# Sheet1.net
KiCad netlist of a schematic drawn in Altium Designer
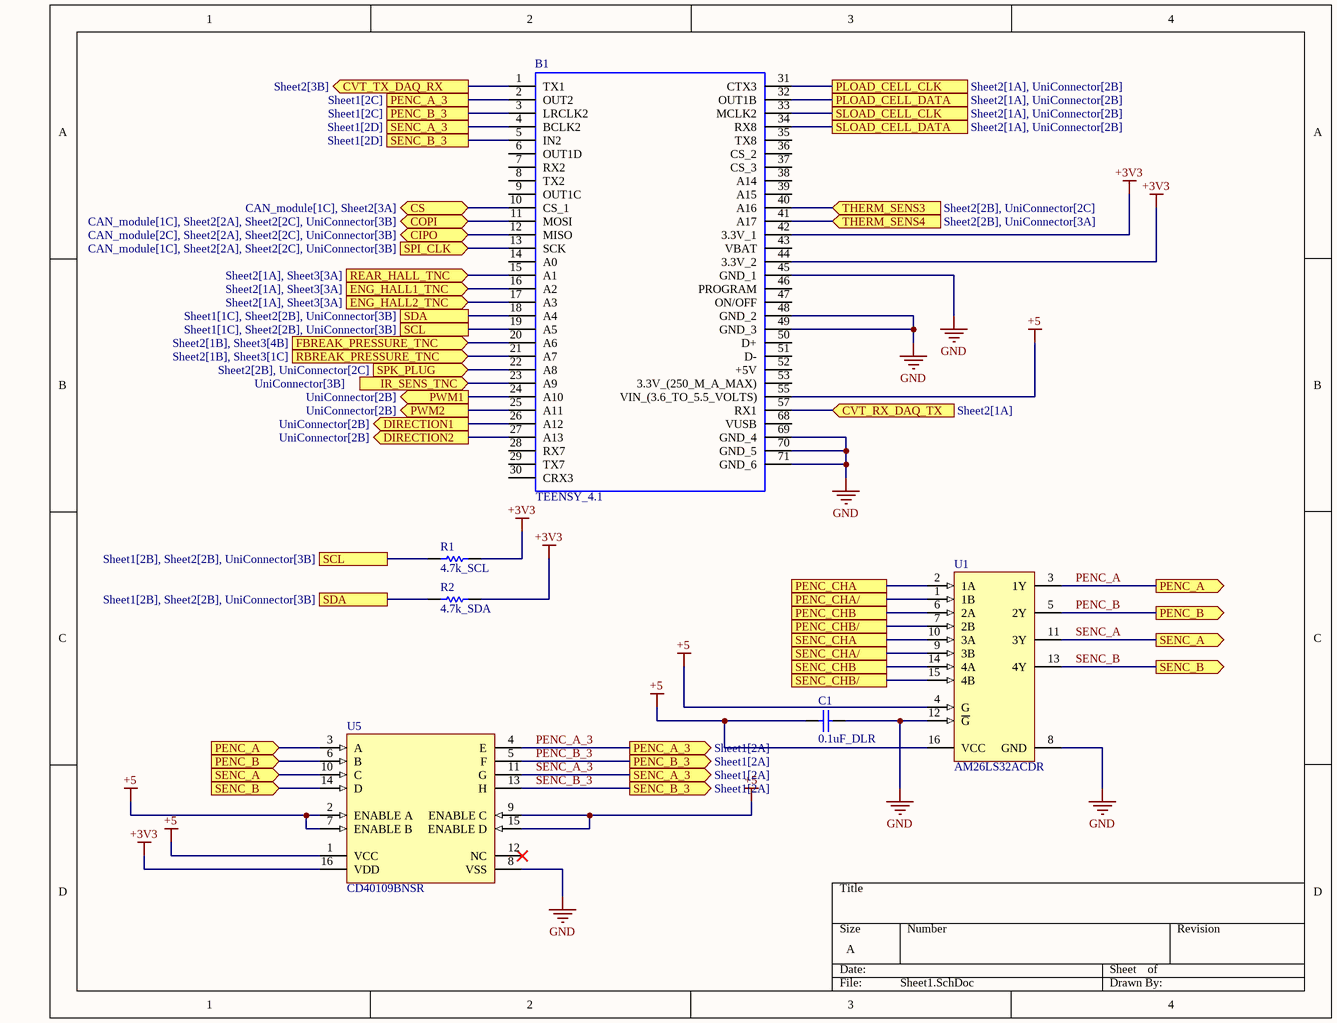
[diagram p0: Sheet1.SchDoc]

(export (version "E")
  (design (tool "Eeschema 10.0.6"))
  (components
    (comp (ref "B1")
      (value "TEENSY_4.1")
      (footprint "TEENSY41")
      (description "Teensy 4.1 Development Board")
      (fields (field (name "MANUFACTURER_PART_NUMBER") "TEENSY 4.1"))
      (libsource (lib "TEENSY_4.1") (part "TEENSY_4.1"))
    )
    (comp (ref "C1")
      (value "0.1uF_DLR")
      (footprint "CAPC2013X94X50LL20T25")
      (fields
        (field (name "MANUFACTURER") "AVX Interconnect / Elco")
        (field (name "PART NUMBER") "08055A6R2CAT2A")
      )
      (libsource (lib "Altium Content Vault") (part "CAP"))
    )
    (comp (ref "R1")
      (value "4.7k_SCL")
      (footprint "RESC2013X60X40LL20T25")
      (fields (field (name "MANUFACTURER") "Panasonic") (field (name "PART NUMBER") "ERA6AEB7870V"))
      (libsource (lib "Altium Content Vault") (part "RES"))
    )
    (comp (ref "R2")
      (value "4.7k_SDA")
      (footprint "RESC2013X60X40LL20T25")
      (fields (field (name "MANUFACTURER") "Panasonic") (field (name "PART NUMBER") "ERA6AEB7870V"))
      (libsource (lib "Altium Content Vault") (part "RES"))
    )
    (comp (ref "U1")
      (value "AM26LS32ACDR")
      (footprint "D0016A_M")
      (fields (field (name "MANUFACTURER") "Texas Instruments"))
      (libsource (lib "Altium Content Vault") (part "TI-AM26LS32AC-SOIC_D-16"))
    )
    (comp (ref "U5")
      (value "CD40109BNSR")
      (footprint "NS0016A_N")
      (fields (field (name "MANUFACTURER") "Texas Instruments"))
      (libsource (lib "Altium Content Vault") (part "TI-CD40109B-16"))
    )
  )
  (nets
    (net (code "1") (name "+3V3") (class "Default")
      (node (ref "B1") (pin "42") (pinfunction "3.3V_1_42") (pintype "passive"))
      (node (ref "B1") (pin "44") (pinfunction "3.3V_2_44") (pintype "passive"))
      (node (ref "R1") (pin "2") (pinfunction "2_2") (pintype "passive"))
      (node (ref "R2") (pin "2") (pinfunction "2_2") (pintype "passive"))
      (node (ref "U5") (pin "16") (pinfunction "VDD_16") (pintype "power_in"))
    )
    (net (code "2") (name "+5") (class "Default")
      (node (ref "B1") (pin "55") (pinfunction "VIN_(3.6_TO_5.5_VOLTS)_55") (pintype "passive"))
      (node (ref "C1") (pin "1") (pinfunction "1_1") (pintype "passive"))
      (node (ref "U1") (pin "16") (pinfunction "VCC_16") (pintype "power_in"))
      (node (ref "U1") (pin "4") (pinfunction "G_4") (pintype "input"))
      (node (ref "U5") (pin "1") (pinfunction "VCC_1") (pintype "power_in"))
      (node (ref "U5") (pin "15") (pinfunction "ENABLE_D_15") (pintype "input"))
      (node (ref "U5") (pin "2") (pinfunction "ENABLE_A_2") (pintype "input"))
      (node (ref "U5") (pin "7") (pinfunction "ENABLE_B_7") (pintype "input"))
      (node (ref "U5") (pin "9") (pinfunction "ENABLE_C_9") (pintype "input"))
    )
    (net (code "3") (name "/CIPO") (class "Default")
      (node (ref "B1") (pin "12") (pinfunction "MISO_12") (pintype "passive"))
    )
    (net (code "4") (name "/COPI") (class "Default")
      (node (ref "B1") (pin "11") (pinfunction "MOSI_11") (pintype "passive"))
    )
    (net (code "5") (name "/CS") (class "Default")
      (node (ref "B1") (pin "10") (pinfunction "CS_1_10") (pintype "passive"))
    )
    (net (code "6") (name "/CVT_RX_DAQ_TX") (class "Default")
      (node (ref "B1") (pin "57") (pinfunction "RX1_57") (pintype "passive"))
    )
    (net (code "7") (name "/CVT_TX_DAQ_RX") (class "Default")
      (node (ref "B1") (pin "1") (pinfunction "TX1_1") (pintype "passive"))
    )
    (net (code "8") (name "/DIRECTION1") (class "Default")
      (node (ref "B1") (pin "26") (pinfunction "A12_26") (pintype "passive"))
    )
    (net (code "9") (name "/DIRECTION2") (class "Default")
      (node (ref "B1") (pin "27") (pinfunction "A13_27") (pintype "passive"))
    )
    (net (code "10") (name "/ENG_HALL1_TNC") (class "Default")
      (node (ref "B1") (pin "16") (pinfunction "A2_16") (pintype "passive"))
    )
    (net (code "11") (name "/ENG_HALL2_TNC") (class "Default")
      (node (ref "B1") (pin "17") (pinfunction "A3_17") (pintype "passive"))
    )
    (net (code "12") (name "/FBREAK_PRESSURE_TNC") (class "Default")
      (node (ref "B1") (pin "20") (pinfunction "A6_20") (pintype "passive"))
    )
    (net (code "13") (name "/IR_SENS_TNC") (class "Default")
      (node (ref "B1") (pin "23") (pinfunction "A9_23") (pintype "passive"))
    )
    (net (code "14") (name "/PENC_A") (class "Default")
      (node (ref "U1") (pin "3") (pinfunction "1Y_3") (pintype "tri_state"))
      (node (ref "U5") (pin "3") (pinfunction "A_3") (pintype "input"))
    )
    (net (code "15") (name "/PENC_A_3") (class "Default")
      (node (ref "B1") (pin "2") (pinfunction "OUT2_2") (pintype "passive"))
      (node (ref "U5") (pin "4") (pinfunction "E_4") (pintype "tri_state"))
    )
    (net (code "16") (name "/PENC_B") (class "Default")
      (node (ref "U1") (pin "5") (pinfunction "2Y_5") (pintype "tri_state"))
      (node (ref "U5") (pin "6") (pinfunction "B_6") (pintype "input"))
    )
    (net (code "17") (name "/PENC_B_3") (class "Default")
      (node (ref "B1") (pin "3") (pinfunction "LRCLK2_3") (pintype "passive"))
      (node (ref "U5") (pin "5") (pinfunction "F_5") (pintype "tri_state"))
    )
    (net (code "18") (name "/PENC_CHA") (class "Default")
      (node (ref "U1") (pin "2") (pinfunction "1A_2") (pintype "input"))
    )
    (net (code "19") (name "/PENC_CHA{slash}") (class "Default")
      (node (ref "U1") (pin "1") (pinfunction "1B_1") (pintype "input"))
    )
    (net (code "20") (name "/PENC_CHB") (class "Default")
      (node (ref "U1") (pin "6") (pinfunction "2A_6") (pintype "input"))
    )
    (net (code "21") (name "/PENC_CHB{slash}") (class "Default")
      (node (ref "U1") (pin "7") (pinfunction "2B_7") (pintype "input"))
    )
    (net (code "22") (name "/PLOAD_CELL_CLK") (class "Default")
      (node (ref "B1") (pin "31") (pinfunction "CTX3_31") (pintype "passive"))
    )
    (net (code "23") (name "/PLOAD_CELL_DATA") (class "Default")
      (node (ref "B1") (pin "32") (pinfunction "OUT1B_32") (pintype "passive"))
    )
    (net (code "24") (name "/PWM1") (class "Default")
      (node (ref "B1") (pin "24") (pinfunction "A10_24") (pintype "passive"))
    )
    (net (code "25") (name "/PWM2") (class "Default")
      (node (ref "B1") (pin "25") (pinfunction "A11_25") (pintype "passive"))
    )
    (net (code "26") (name "/RBREAK_PRESSURE_TNC") (class "Default")
      (node (ref "B1") (pin "21") (pinfunction "A7_21") (pintype "passive"))
    )
    (net (code "27") (name "/REAR_HALL_TNC") (class "Default")
      (node (ref "B1") (pin "15") (pinfunction "A1_15") (pintype "passive"))
    )
    (net (code "28") (name "/SCL") (class "Default")
      (node (ref "B1") (pin "19") (pinfunction "A5_19") (pintype "passive"))
      (node (ref "R1") (pin "1") (pinfunction "1_1") (pintype "passive"))
    )
    (net (code "29") (name "/SDA") (class "Default")
      (node (ref "B1") (pin "18") (pinfunction "A4_18") (pintype "passive"))
      (node (ref "R2") (pin "1") (pinfunction "1_1") (pintype "passive"))
    )
    (net (code "30") (name "/SENC_A") (class "Default")
      (node (ref "U1") (pin "11") (pinfunction "3Y_11") (pintype "tri_state"))
      (node (ref "U5") (pin "10") (pinfunction "C_10") (pintype "input"))
    )
    (net (code "31") (name "/SENC_A_3") (class "Default")
      (node (ref "B1") (pin "4") (pinfunction "BCLK2_4") (pintype "passive"))
      (node (ref "U5") (pin "11") (pinfunction "G_11") (pintype "tri_state"))
    )
    (net (code "32") (name "/SENC_B") (class "Default")
      (node (ref "U1") (pin "13") (pinfunction "4Y_13") (pintype "tri_state"))
      (node (ref "U5") (pin "14") (pinfunction "D_14") (pintype "input"))
    )
    (net (code "33") (name "/SENC_B_3") (class "Default")
      (node (ref "B1") (pin "5") (pinfunction "IN2_5") (pintype "passive"))
      (node (ref "U5") (pin "13") (pinfunction "H_13") (pintype "tri_state"))
    )
    (net (code "34") (name "/SENC_CHA") (class "Default")
      (node (ref "U1") (pin "10") (pinfunction "3A_10") (pintype "input"))
    )
    (net (code "35") (name "/SENC_CHA{slash}") (class "Default")
      (node (ref "U1") (pin "9") (pinfunction "3B_9") (pintype "input"))
    )
    (net (code "36") (name "/SENC_CHB") (class "Default")
      (node (ref "U1") (pin "14") (pinfunction "4A_14") (pintype "input"))
    )
    (net (code "37") (name "/SENC_CHB{slash}") (class "Default")
      (node (ref "U1") (pin "15") (pinfunction "4B_15") (pintype "input"))
    )
    (net (code "38") (name "/SLOAD_CELL_CLK") (class "Default")
      (node (ref "B1") (pin "33") (pinfunction "MCLK2_33") (pintype "passive"))
    )
    (net (code "39") (name "/SLOAD_CELL_DATA") (class "Default")
      (node (ref "B1") (pin "34") (pinfunction "RX8_34") (pintype "passive"))
    )
    (net (code "40") (name "/SPI_CLK") (class "Default")
      (node (ref "B1") (pin "13") (pinfunction "SCK_13") (pintype "passive"))
    )
    (net (code "41") (name "/SPK_PLUG") (class "Default")
      (node (ref "B1") (pin "22") (pinfunction "A8_22") (pintype "passive"))
    )
    (net (code "42") (name "/THERM_SENS3") (class "Default")
      (node (ref "B1") (pin "40") (pinfunction "A16_40") (pintype "passive"))
    )
    (net (code "43") (name "/THERM_SENS4") (class "Default")
      (node (ref "B1") (pin "41") (pinfunction "A17_41") (pintype "passive"))
    )
    (net (code "44") (name "GND") (class "Default")
      (node (ref "B1") (pin "45") (pinfunction "GND_1_45") (pintype "passive"))
      (node (ref "B1") (pin "48") (pinfunction "GND_2_48") (pintype "passive"))
      (node (ref "B1") (pin "49") (pinfunction "GND_3_49") (pintype "passive"))
      (node (ref "B1") (pin "69") (pinfunction "GND_4_69") (pintype "passive"))
      (node (ref "B1") (pin "70") (pinfunction "GND_5_70") (pintype "passive"))
      (node (ref "B1") (pin "71") (pinfunction "GND_6_71") (pintype "passive"))
      (node (ref "C1") (pin "2") (pinfunction "2_2") (pintype "passive"))
      (node (ref "U1") (pin "12") (pinfunction "~{G}_12") (pintype "input"))
      (node (ref "U1") (pin "8") (pinfunction "GND_8") (pintype "power_in"))
      (node (ref "U5") (pin "8") (pinfunction "VSS_8") (pintype "power_in"))
    )
    (net (code "45") (name "unconnected-(B1-+5V-Pad52)") (class "Default")
      (node (ref "B1") (pin "52") (pinfunction "+5V_52") (pintype "passive"))
    )
    (net (code "46") (name "unconnected-(B1-3.3V_(250_M_A_MAX)-Pad53)") (class "Default")
      (node (ref "B1") (pin "53") (pinfunction "3.3V_(250_M_A_MAX)_53") (pintype "passive"))
    )
    (net (code "47") (name "unconnected-(B1-A0-Pad14)") (class "Default")
      (node (ref "B1") (pin "14") (pinfunction "A0_14") (pintype "passive"))
    )
    (net (code "48") (name "unconnected-(B1-A14-Pad38)") (class "Default")
      (node (ref "B1") (pin "38") (pinfunction "A14_38") (pintype "passive"))
    )
    (net (code "49") (name "unconnected-(B1-A15-Pad39)") (class "Default")
      (node (ref "B1") (pin "39") (pinfunction "A15_39") (pintype "passive"))
    )
    (net (code "50") (name "unconnected-(B1-CRX3-Pad30)") (class "Default")
      (node (ref "B1") (pin "30") (pinfunction "CRX3_30") (pintype "passive"))
    )
    (net (code "51") (name "unconnected-(B1-CS_2-Pad36)") (class "Default")
      (node (ref "B1") (pin "36") (pinfunction "CS_2_36") (pintype "passive"))
    )
    (net (code "52") (name "unconnected-(B1-CS_3-Pad37)") (class "Default")
      (node (ref "B1") (pin "37") (pinfunction "CS_3_37") (pintype "passive"))
    )
    (net (code "53") (name "unconnected-(B1-D+-Pad50)") (class "Default")
      (node (ref "B1") (pin "50") (pinfunction "D+_50") (pintype "passive"))
    )
    (net (code "54") (name "unconnected-(B1-D--Pad51)") (class "Default")
      (node (ref "B1") (pin "51") (pinfunction "D-_51") (pintype "passive"))
    )
    (net (code "55") (name "unconnected-(B1-ON{slash}OFF-Pad47)") (class "Default")
      (node (ref "B1") (pin "47") (pinfunction "ON/OFF_47") (pintype "passive"))
    )
    (net (code "56") (name "unconnected-(B1-OUT1C-Pad9)") (class "Default")
      (node (ref "B1") (pin "9") (pinfunction "OUT1C_9") (pintype "passive"))
    )
    (net (code "57") (name "unconnected-(B1-OUT1D-Pad6)") (class "Default")
      (node (ref "B1") (pin "6") (pinfunction "OUT1D_6") (pintype "passive"))
    )
    (net (code "58") (name "unconnected-(B1-PROGRAM-Pad46)") (class "Default")
      (node (ref "B1") (pin "46") (pinfunction "PROGRAM_46") (pintype "passive"))
    )
    (net (code "59") (name "unconnected-(B1-RX2-Pad7)") (class "Default")
      (node (ref "B1") (pin "7") (pinfunction "RX2_7") (pintype "passive"))
    )
    (net (code "60") (name "unconnected-(B1-RX7-Pad28)") (class "Default")
      (node (ref "B1") (pin "28") (pinfunction "RX7_28") (pintype "passive"))
    )
    (net (code "61") (name "unconnected-(B1-TX2-Pad8)") (class "Default")
      (node (ref "B1") (pin "8") (pinfunction "TX2_8") (pintype "passive"))
    )
    (net (code "62") (name "unconnected-(B1-TX7-Pad29)") (class "Default")
      (node (ref "B1") (pin "29") (pinfunction "TX7_29") (pintype "passive"))
    )
    (net (code "63") (name "unconnected-(B1-TX8-Pad35)") (class "Default")
      (node (ref "B1") (pin "35") (pinfunction "TX8_35") (pintype "passive"))
    )
    (net (code "64") (name "unconnected-(B1-VBAT-Pad43)") (class "Default")
      (node (ref "B1") (pin "43") (pinfunction "VBAT_43") (pintype "passive"))
    )
    (net (code "65") (name "unconnected-(B1-VUSB-Pad68)") (class "Default")
      (node (ref "B1") (pin "68") (pinfunction "VUSB_68") (pintype "passive"))
    )
    (net (code "66") (name "unconnected-(U5-NC-Pad12)") (class "Default")
      (node (ref "U5") (pin "12") (pinfunction "NC_12") (pintype "passive+no_connect"))
    )
  )
)
